# V2.net
KiCad netlist of a schematic drawn in EAGLE
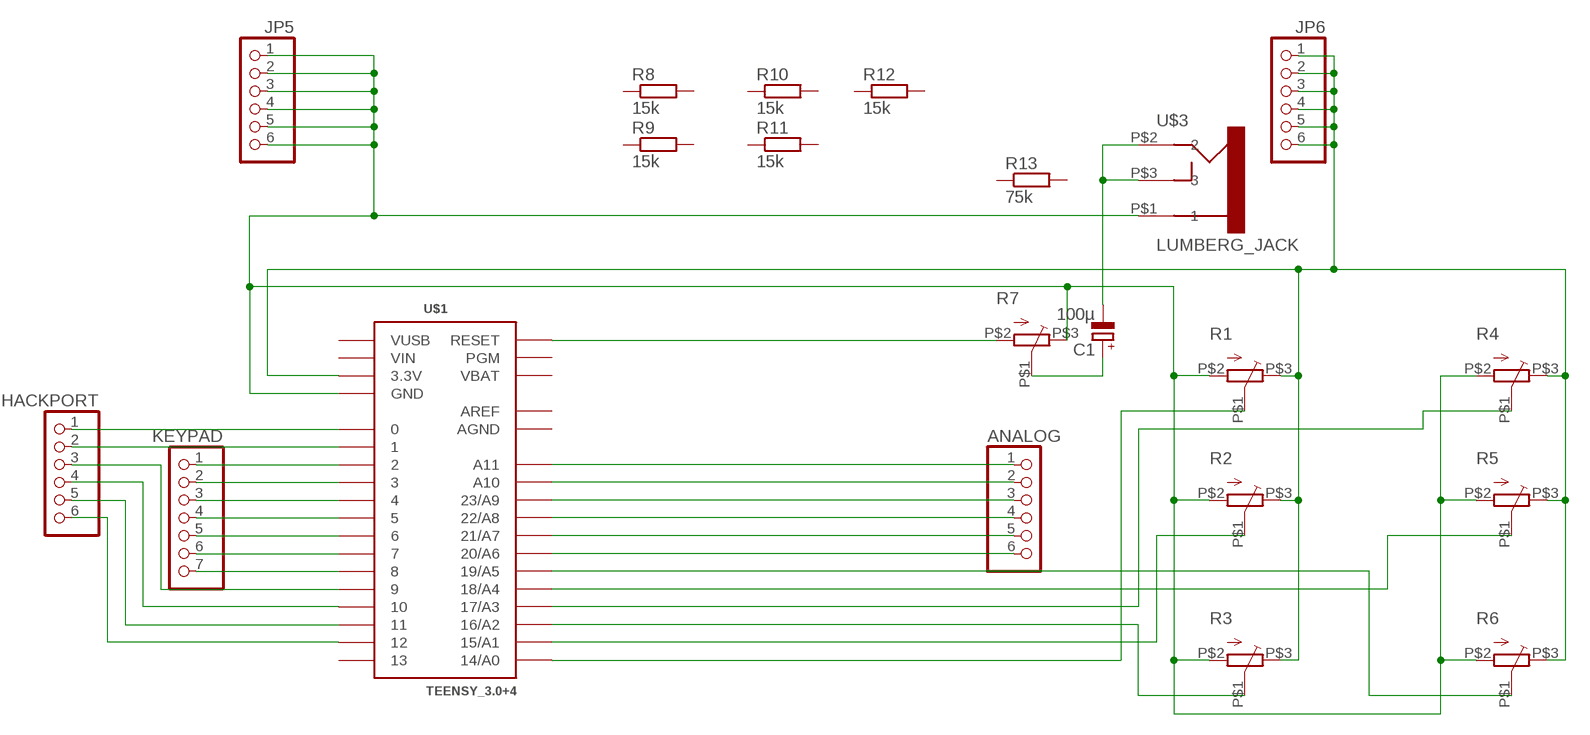
[diagram p0: schematic, sheet 1]

(export (version "E")
  (design (tool "Eeschema 10.0.6"))
  (components
    (comp (ref "ANALOG")
      (value "PINHD-1X6")
      (footprint "eagle-import:1X06")
      (libsource (lib "eagle-import") (part "PINHD-1X6"))
    )
    (comp (ref "C1")
      (value "100µ")
      (footprint "eagle-import:E2,5-6")
      (libsource (lib "eagle-import") (part "CPOL-EUE2.5-6"))
    )
    (comp (ref "HACKPORT")
      (value "PINHD-1X6")
      (footprint "eagle-import:1X06")
      (libsource (lib "eagle-import") (part "PINHD-1X6"))
    )
    (comp (ref "JP5")
      (value "PINHD-1X6")
      (footprint "eagle-import:1X06")
      (libsource (lib "eagle-import") (part "PINHD-1X6"))
    )
    (comp (ref "JP6")
      (value "PINHD-1X6")
      (footprint "eagle-import:1X06")
      (libsource (lib "eagle-import") (part "PINHD-1X6"))
    )
    (comp (ref "KEYPAD")
      (value "PINHD-1X7")
      (footprint "eagle-import:1X07")
      (libsource (lib "eagle-import") (part "PINHD-1X7"))
    )
    (comp (ref "R1")
      (value "STR09K113")
      (footprint "eagle-import:STR09K113")
      (libsource (lib "eagle-import") (part "STR09K113"))
    )
    (comp (ref "R2")
      (value "STR09K113")
      (footprint "eagle-import:STR09K113")
      (libsource (lib "eagle-import") (part "STR09K113"))
    )
    (comp (ref "R3")
      (value "STR09K113")
      (footprint "eagle-import:STR09K113")
      (libsource (lib "eagle-import") (part "STR09K113"))
    )
    (comp (ref "R4")
      (value "STR09K113")
      (footprint "eagle-import:STR09K113")
      (libsource (lib "eagle-import") (part "STR09K113"))
    )
    (comp (ref "R5")
      (value "STR09K113")
      (footprint "eagle-import:STR09K113")
      (libsource (lib "eagle-import") (part "STR09K113"))
    )
    (comp (ref "R6")
      (value "STR09K113")
      (footprint "eagle-import:STR09K113")
      (libsource (lib "eagle-import") (part "STR09K113"))
    )
    (comp (ref "R7")
      (value "STR09K113")
      (footprint "eagle-import:STR09K113")
      (libsource (lib "eagle-import") (part "STR09K113"))
    )
    (comp (ref "R8")
      (value "15k")
      (footprint "eagle-import:0309_12")
      (libsource (lib "eagle-import") (part "R-EU_0309/12"))
    )
    (comp (ref "R9")
      (value "15k")
      (footprint "eagle-import:0309_12")
      (libsource (lib "eagle-import") (part "R-EU_0309/12"))
    )
    (comp (ref "R10")
      (value "15k")
      (footprint "eagle-import:0309_12")
      (libsource (lib "eagle-import") (part "R-EU_0309/12"))
    )
    (comp (ref "R11")
      (value "15k")
      (footprint "eagle-import:0309_12")
      (libsource (lib "eagle-import") (part "R-EU_0309/12"))
    )
    (comp (ref "R12")
      (value "15k")
      (footprint "eagle-import:0309_12")
      (libsource (lib "eagle-import") (part "R-EU_0309/12"))
    )
    (comp (ref "R13")
      (value "75k")
      (footprint "eagle-import:0309_12")
      (libsource (lib "eagle-import") (part "R-EU_0309/12"))
    )
    (comp (ref "U$1")
      (value "TEENSY_3.0+4")
      (footprint "eagle-import:TEENSY_3.0+4")
      (libsource (lib "eagle-import") (part "TEENSY_3.0+4"))
    )
    (comp (ref "U$3")
      (value "LUMBERG_JACK")
      (footprint "eagle-import:JACK_CON")
      (libsource (lib "eagle-import") (part "LUMBERG_JACK"))
    )
  )
  (nets
    (net (code "1") (name "/AGND") (class "Default")
      (node (ref "U$1") (pin "AGND") (pinfunction "AGND_AGND") (pintype "power_in"))
    )
    (net (code "2") (name "/AREF") (class "Default")
      (node (ref "U$1") (pin "AREF") (pinfunction "AREF_AREF") (pintype "power_in"))
    )
    (net (code "3") (name "/VBAT") (class "Default")
      (node (ref "U$1") (pin "VBAT") (pinfunction "VBAT_VBAT") (pintype "power_in"))
    )
    (net (code "4") (name "/VIN") (class "Default")
      (node (ref "U$1") (pin "VIN") (pinfunction "VIN_VIN") (pintype "power_in"))
    )
    (net (code "5") (name "/VUSB") (class "Default")
      (node (ref "U$1") (pin "VUSB") (pinfunction "VUSB_VUSB") (pintype "power_in"))
    )
    (net (code "6") (name "Net-(ANALOG-Pad1)") (class "Default")
      (node (ref "ANALOG") (pin "1") (pinfunction "1_1") (pintype "passive"))
      (node (ref "U$1") (pin "A11") (pinfunction "A11_A11") (pintype "bidirectional"))
    )
    (net (code "7") (name "Net-(ANALOG-Pad2)") (class "Default")
      (node (ref "ANALOG") (pin "2") (pinfunction "2_2") (pintype "passive"))
      (node (ref "U$1") (pin "A10") (pinfunction "A10_A10") (pintype "bidirectional"))
    )
    (net (code "8") (name "Net-(ANALOG-Pad3)") (class "Default")
      (node (ref "ANALOG") (pin "3") (pinfunction "3_3") (pintype "passive"))
      (node (ref "U$1") (pin "23/A9") (pinfunction "23/A9_23/A9") (pintype "bidirectional"))
    )
    (net (code "9") (name "Net-(ANALOG-Pad4)") (class "Default")
      (node (ref "ANALOG") (pin "4") (pinfunction "4_4") (pintype "passive"))
      (node (ref "U$1") (pin "22/A8") (pinfunction "22/A8_22/A8") (pintype "bidirectional"))
    )
    (net (code "10") (name "Net-(ANALOG-Pad5)") (class "Default")
      (node (ref "ANALOG") (pin "5") (pinfunction "5_5") (pintype "passive"))
      (node (ref "U$1") (pin "21/A7") (pinfunction "21/A7_21/A7") (pintype "bidirectional"))
    )
    (net (code "11") (name "Net-(ANALOG-Pad6)") (class "Default")
      (node (ref "ANALOG") (pin "6") (pinfunction "6_6") (pintype "passive"))
      (node (ref "U$1") (pin "20/A6") (pinfunction "20/A6_20/A6") (pintype "bidirectional"))
    )
    (net (code "12") (name "Net-(HACKPORT-Pad1)") (class "Default")
      (node (ref "HACKPORT") (pin "1") (pinfunction "1_1") (pintype "passive"))
      (node (ref "U$1") (pin "0") (pinfunction "0_0") (pintype "bidirectional"))
    )
    (net (code "13") (name "Net-(HACKPORT-Pad2)") (class "Default")
      (node (ref "HACKPORT") (pin "2") (pinfunction "2_2") (pintype "passive"))
      (node (ref "U$1") (pin "1") (pinfunction "1_1") (pintype "bidirectional"))
    )
    (net (code "14") (name "Net-(HACKPORT-Pad3)") (class "Default")
      (node (ref "HACKPORT") (pin "3") (pinfunction "3_3") (pintype "passive"))
      (node (ref "U$1") (pin "9") (pinfunction "9_9") (pintype "bidirectional"))
    )
    (net (code "15") (name "Net-(HACKPORT-Pad4)") (class "Default")
      (node (ref "HACKPORT") (pin "4") (pinfunction "4_4") (pintype "passive"))
      (node (ref "U$1") (pin "10") (pinfunction "10_10") (pintype "bidirectional"))
    )
    (net (code "16") (name "Net-(HACKPORT-Pad5)") (class "Default")
      (node (ref "HACKPORT") (pin "5") (pinfunction "5_5") (pintype "passive"))
      (node (ref "U$1") (pin "11") (pinfunction "11_11") (pintype "bidirectional"))
    )
    (net (code "17") (name "Net-(HACKPORT-Pad6)") (class "Default")
      (node (ref "HACKPORT") (pin "6") (pinfunction "6_6") (pintype "passive"))
      (node (ref "U$1") (pin "12") (pinfunction "12_12") (pintype "bidirectional"))
    )
    (net (code "18") (name "Net-(KEYPAD-Pad1)") (class "Default")
      (node (ref "KEYPAD") (pin "1") (pinfunction "1_1") (pintype "passive"))
      (node (ref "U$1") (pin "2") (pinfunction "2_2") (pintype "bidirectional"))
    )
    (net (code "19") (name "Net-(KEYPAD-Pad2)") (class "Default")
      (node (ref "KEYPAD") (pin "2") (pinfunction "2_2") (pintype "passive"))
      (node (ref "U$1") (pin "3") (pinfunction "3_3") (pintype "bidirectional"))
    )
    (net (code "20") (name "Net-(KEYPAD-Pad3)") (class "Default")
      (node (ref "KEYPAD") (pin "3") (pinfunction "3_3") (pintype "passive"))
      (node (ref "U$1") (pin "4") (pinfunction "4_4") (pintype "bidirectional"))
    )
    (net (code "21") (name "Net-(KEYPAD-Pad4)") (class "Default")
      (node (ref "KEYPAD") (pin "4") (pinfunction "4_4") (pintype "passive"))
      (node (ref "U$1") (pin "5") (pinfunction "5_5") (pintype "bidirectional"))
    )
    (net (code "22") (name "Net-(KEYPAD-Pad5)") (class "Default")
      (node (ref "KEYPAD") (pin "5") (pinfunction "5_5") (pintype "passive"))
      (node (ref "U$1") (pin "6") (pinfunction "6_6") (pintype "bidirectional"))
    )
    (net (code "23") (name "Net-(KEYPAD-Pad6)") (class "Default")
      (node (ref "KEYPAD") (pin "6") (pinfunction "6_6") (pintype "passive"))
      (node (ref "U$1") (pin "7") (pinfunction "7_7") (pintype "bidirectional"))
    )
    (net (code "24") (name "Net-(KEYPAD-Pad7)") (class "Default")
      (node (ref "KEYPAD") (pin "7") (pinfunction "7_7") (pintype "passive"))
      (node (ref "U$1") (pin "8") (pinfunction "8_8") (pintype "bidirectional"))
    )
    (net (code "25") (name "Net-(R1-E)") (class "Default")
      (node (ref "JP6") (pin "1") (pinfunction "1_1") (pintype "passive"))
      (node (ref "JP6") (pin "2") (pinfunction "2_2") (pintype "passive"))
      (node (ref "JP6") (pin "3") (pinfunction "3_3") (pintype "passive"))
      (node (ref "JP6") (pin "4") (pinfunction "4_4") (pintype "passive"))
      (node (ref "JP6") (pin "5") (pinfunction "5_5") (pintype "passive"))
      (node (ref "JP6") (pin "6") (pinfunction "6_6") (pintype "passive"))
      (node (ref "R1") (pin "P$3") (pinfunction "E_P$3") (pintype "passive"))
      (node (ref "R2") (pin "P$3") (pinfunction "E_P$3") (pintype "passive"))
      (node (ref "R3") (pin "P$3") (pinfunction "E_P$3") (pintype "passive"))
      (node (ref "R4") (pin "P$3") (pinfunction "E_P$3") (pintype "passive"))
      (node (ref "R5") (pin "P$3") (pinfunction "E_P$3") (pintype "passive"))
      (node (ref "R6") (pin "P$3") (pinfunction "E_P$3") (pintype "passive"))
      (node (ref "U$1") (pin "3.3V") (pinfunction "3.3V_3.3V") (pintype "power_in"))
      (node (ref "U$1") (pin "3.3V1") (pinfunction "3.3V_3.3V1") (pintype "power_in"))
    )
    (net (code "26") (name "Net-(R1-S)") (class "Default")
      (node (ref "JP5") (pin "1") (pinfunction "1_1") (pintype "passive"))
      (node (ref "JP5") (pin "2") (pinfunction "2_2") (pintype "passive"))
      (node (ref "JP5") (pin "3") (pinfunction "3_3") (pintype "passive"))
      (node (ref "JP5") (pin "4") (pinfunction "4_4") (pintype "passive"))
      (node (ref "JP5") (pin "5") (pinfunction "5_5") (pintype "passive"))
      (node (ref "JP5") (pin "6") (pinfunction "6_6") (pintype "passive"))
      (node (ref "R1") (pin "P$2") (pinfunction "S_P$2") (pintype "passive"))
      (node (ref "R2") (pin "P$2") (pinfunction "S_P$2") (pintype "passive"))
      (node (ref "R3") (pin "P$2") (pinfunction "S_P$2") (pintype "passive"))
      (node (ref "R4") (pin "P$2") (pinfunction "S_P$2") (pintype "passive"))
      (node (ref "R5") (pin "P$2") (pinfunction "S_P$2") (pintype "passive"))
      (node (ref "R6") (pin "P$2") (pinfunction "S_P$2") (pintype "passive"))
      (node (ref "R7") (pin "P$3") (pinfunction "E_P$3") (pintype "passive"))
      (node (ref "U$1") (pin "GND") (pinfunction "GND_GND") (pintype "power_in"))
      (node (ref "U$1") (pin "GND1") (pinfunction "GND_GND1") (pintype "power_in"))
      (node (ref "U$3") (pin "P$1") (pinfunction "1_P$1") (pintype "passive"))
    )
    (net (code "27") (name "Net-(R1-W)") (class "Default")
      (node (ref "R1") (pin "P$1") (pinfunction "W_P$1") (pintype "passive"))
      (node (ref "U$1") (pin "14/A0") (pinfunction "14/A0_14/A0") (pintype "bidirectional"))
    )
    (net (code "28") (name "Net-(R2-W)") (class "Default")
      (node (ref "R2") (pin "P$1") (pinfunction "W_P$1") (pintype "passive"))
      (node (ref "U$1") (pin "15/A1") (pinfunction "15/A1_15/A1") (pintype "bidirectional"))
    )
    (net (code "29") (name "Net-(R3-W)") (class "Default")
      (node (ref "R3") (pin "P$1") (pinfunction "W_P$1") (pintype "passive"))
      (node (ref "U$1") (pin "16/A2") (pinfunction "16/A2_16/A2") (pintype "bidirectional"))
    )
    (net (code "30") (name "Net-(R4-W)") (class "Default")
      (node (ref "R4") (pin "P$1") (pinfunction "W_P$1") (pintype "passive"))
      (node (ref "U$1") (pin "17/A3") (pinfunction "17/A3_17/A3") (pintype "bidirectional"))
    )
    (net (code "31") (name "Net-(R5-W)") (class "Default")
      (node (ref "R5") (pin "P$1") (pinfunction "W_P$1") (pintype "passive"))
      (node (ref "U$1") (pin "18/A4") (pinfunction "18/A4_18/A4") (pintype "bidirectional"))
    )
    (net (code "32") (name "Net-(R6-W)") (class "Default")
      (node (ref "R6") (pin "P$1") (pinfunction "W_P$1") (pintype "passive"))
      (node (ref "U$1") (pin "19/A5") (pinfunction "19/A5_19/A5") (pintype "bidirectional"))
    )
    (net (code "33") (name "Net-(R7-S)") (class "Default")
      (node (ref "R7") (pin "P$2") (pinfunction "S_P$2") (pintype "passive"))
      (node (ref "U$1") (pin "RESET") (pinfunction "RESET_RESET") (pintype "bidirectional"))
    )
    (net (code "34") (name "Net-(R7-W)") (class "Default")
      (node (ref "C1") (pin "+") (pinfunction "+_+") (pintype "passive"))
      (node (ref "R7") (pin "P$1") (pinfunction "W_P$1") (pintype "passive"))
    )
    (net (code "35") (name "Net-(U$3-2)") (class "Default")
      (node (ref "C1") (pin "-") (pinfunction "-_-") (pintype "passive"))
      (node (ref "U$3") (pin "P$2") (pinfunction "2_P$2") (pintype "passive"))
      (node (ref "U$3") (pin "P$3") (pinfunction "3_P$3") (pintype "passive"))
    )
    (net (code "36") (name "unconnected-(R8-Pad1)") (class "Default")
      (node (ref "R8") (pin "1") (pinfunction "1_1") (pintype "passive"))
    )
    (net (code "37") (name "unconnected-(R8-Pad2)") (class "Default")
      (node (ref "R8") (pin "2") (pinfunction "2_2") (pintype "passive"))
    )
    (net (code "38") (name "unconnected-(R9-Pad1)") (class "Default")
      (node (ref "R9") (pin "1") (pinfunction "1_1") (pintype "passive"))
    )
    (net (code "39") (name "unconnected-(R9-Pad2)") (class "Default")
      (node (ref "R9") (pin "2") (pinfunction "2_2") (pintype "passive"))
    )
    (net (code "40") (name "unconnected-(R10-Pad1)") (class "Default")
      (node (ref "R10") (pin "1") (pinfunction "1_1") (pintype "passive"))
    )
    (net (code "41") (name "unconnected-(R10-Pad2)") (class "Default")
      (node (ref "R10") (pin "2") (pinfunction "2_2") (pintype "passive"))
    )
    (net (code "42") (name "unconnected-(R11-Pad1)") (class "Default")
      (node (ref "R11") (pin "1") (pinfunction "1_1") (pintype "passive"))
    )
    (net (code "43") (name "unconnected-(R11-Pad2)") (class "Default")
      (node (ref "R11") (pin "2") (pinfunction "2_2") (pintype "passive"))
    )
    (net (code "44") (name "unconnected-(R12-Pad1)") (class "Default")
      (node (ref "R12") (pin "1") (pinfunction "1_1") (pintype "passive"))
    )
    (net (code "45") (name "unconnected-(R12-Pad2)") (class "Default")
      (node (ref "R12") (pin "2") (pinfunction "2_2") (pintype "passive"))
    )
    (net (code "46") (name "unconnected-(R13-Pad1)") (class "Default")
      (node (ref "R13") (pin "1") (pinfunction "1_1") (pintype "passive"))
    )
    (net (code "47") (name "unconnected-(R13-Pad2)") (class "Default")
      (node (ref "R13") (pin "2") (pinfunction "2_2") (pintype "passive"))
    )
    (net (code "48") (name "unconnected-(U$1-Pad13)") (class "Default")
      (node (ref "U$1") (pin "13") (pinfunction "13_13") (pintype "bidirectional"))
    )
    (net (code "49") (name "unconnected-(U$1-PadPGM)") (class "Default")
      (node (ref "U$1") (pin "PGM") (pinfunction "PGM_PGM") (pintype "bidirectional"))
    )
  )
)
